# Sheet1.net
KiCad netlist of a schematic drawn in Altium Designer
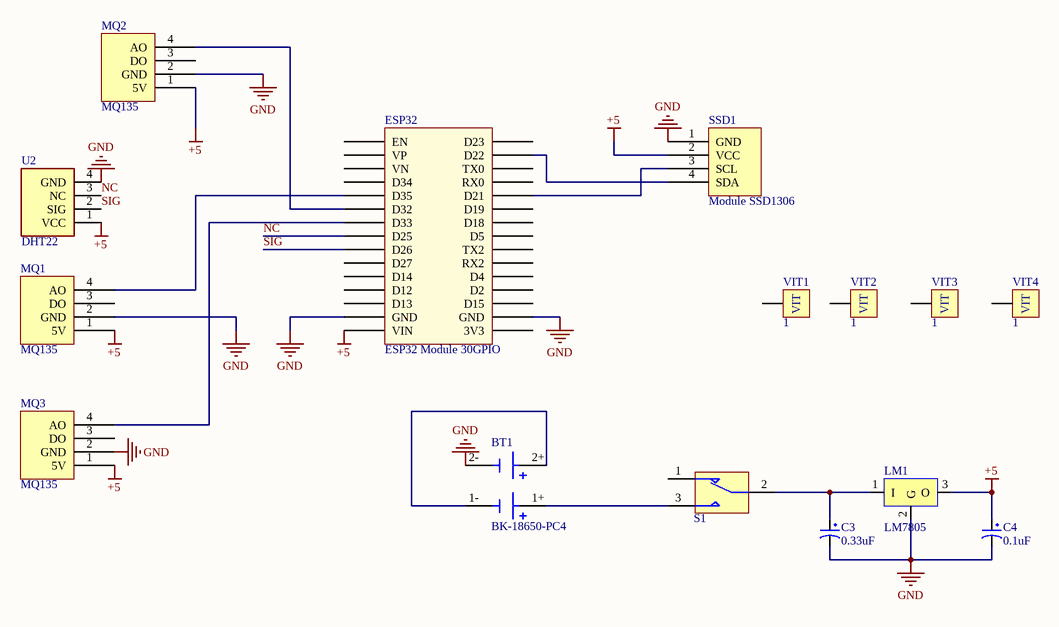
[diagram p0: Sheet1.SchDoc]

(export (version "E")
  (design (tool "Eeschema 10.0.6"))
  (components
    (comp (ref "BT1")
      (value "BK-18650-PC4")
      (footprint "BAT_BK-18650-PC4")
      (description "Battery Holder (Open) 18650 2 Cell PC Pin")
      (libsource (lib "MrKoi_Lib_Sch") (part "BK-18650-PC4"))
    )
    (comp (ref "C3")
      (value "0.33uF")
      (footprint "tu hoa 5mm")
      (description "Cắm")
      (libsource (lib "Tu dien") (part "Tu Hoa 0.33uF 50V 5x11"))
    )
    (comp (ref "C4")
      (value "0.1uF")
      (footprint "tu hoa 5mm")
      (description "Cắm")
      (libsource (lib "Tu dien") (part "Tu Hoa 0.1uF 50V 5x11"))
    )
    (comp (ref "ESP32")
      (value "ESP32 Module 30GPIO")
      (footprint "ESP32 Module 30GPIO_v2")
      (libsource (lib "Module1") (part "ESP32 Module 30GPIO"))
    )
    (comp (ref "LM1")
      (value "LM7805")
      (footprint "TO220NH")
      (description "IC REG LDO 5V 1A TO220-3")
      (libsource (lib "IC") (part "LM78xx"))
    )
    (comp (ref "MQ1")
      (value "MQ135")
      (footprint "MyLibrary:MQ135")
      (libsource (lib "MyLibrary") (part "MQ135"))
    )
    (comp (ref "MQ2")
      (value "MQ135")
      (footprint "MyLibrary:MQ135")
      (libsource (lib "MyLibrary") (part "MQ135"))
    )
    (comp (ref "MQ3")
      (value "MQ135")
      (footprint "MyLibrary:MQ135")
      (libsource (lib "MyLibrary") (part "MQ135"))
    )
    (comp (ref "S1")
      (value "Switch SPDT_Subminiator")
      (footprint "SPDT Subminiator")
      (description "Subminiator SPDT Switch")
      (libsource (lib "iDr.ALTIUM") (part "Switch SPDT_Subminiator"))
    )
    (comp (ref "SSD1")
      (value "Module SSD1306")
      (footprint "Module SSD1306")
      (libsource (lib "MrKoi_Lib_Sch") (part "Module SSD1306"))
    )
    (comp (ref "U2")
      (value "DHT22")
      (footprint "Sensors:DHT22_180")
      (description "SENSOR HUMIDITY/TEMPERATURE")
      (libsource (lib "Sensors") (part "DHT22"))
    )
    (comp (ref "VIT1")
      (value "1")
      (footprint "Screw octagon 3.81mm")
      (description "Vit xuyen lo")
      (libsource (lib "Connector") (part "VIT"))
    )
    (comp (ref "VIT2")
      (value "1")
      (footprint "Screw octagon 3.81mm")
      (description "Vit xuyen lo")
      (libsource (lib "Connector") (part "VIT"))
    )
    (comp (ref "VIT3")
      (value "1")
      (footprint "Screw octagon 3.81mm")
      (description "Vit xuyen lo")
      (libsource (lib "Connector") (part "VIT"))
    )
    (comp (ref "VIT4")
      (value "1")
      (footprint "Screw octagon 3.81mm")
      (description "Vit xuyen lo")
      (libsource (lib "Connector") (part "VIT"))
    )
  )
  (nets
    (net (code "1") (name "+5") (class "Default")
      (node (ref "C4") (pin "1") (pinfunction "1_1") (pintype "passive"))
      (node (ref "ESP32") (pin "30") (pinfunction "VIN_30") (pintype "passive"))
      (node (ref "LM1") (pin "3") (pinfunction "O_3") (pintype "power_in"))
      (node (ref "MQ1") (pin "1") (pinfunction "5V_1") (pintype "passive"))
      (node (ref "MQ2") (pin "1") (pinfunction "5V_1") (pintype "passive"))
      (node (ref "MQ3") (pin "1") (pinfunction "5V_1") (pintype "passive"))
      (node (ref "SSD1") (pin "2") (pinfunction "VCC_2") (pintype "passive"))
      (node (ref "U2") (pin "1") (pinfunction "VCC_1") (pintype "passive"))
    )
    (net (code "2") (name "/NC") (class "Default")
      (node (ref "ESP32") (pin "23") (pinfunction "D25_23") (pintype "passive"))
      (node (ref "U2") (pin "3") (pinfunction "NC_3") (pintype "passive"))
    )
    (net (code "3") (name "/SIG") (class "Default")
      (node (ref "ESP32") (pin "24") (pinfunction "D26_24") (pintype "passive"))
      (node (ref "U2") (pin "2") (pinfunction "SIG_2") (pintype "passive"))
    )
    (net (code "4") (name "GND") (class "Default")
      (node (ref "BT1") (pin "2-") (pinfunction "2-_2-") (pintype "passive"))
      (node (ref "C3") (pin "2") (pinfunction "2_2") (pintype "passive"))
      (node (ref "C4") (pin "2") (pinfunction "2_2") (pintype "passive"))
      (node (ref "ESP32") (pin "14") (pinfunction "GND_14") (pintype "passive"))
      (node (ref "ESP32") (pin "29") (pinfunction "GND_29") (pintype "passive"))
      (node (ref "LM1") (pin "2") (pinfunction "G_2") (pintype "power_in"))
      (node (ref "MQ1") (pin "2") (pinfunction "GND_2") (pintype "passive"))
      (node (ref "MQ2") (pin "2") (pinfunction "GND_2") (pintype "passive"))
      (node (ref "MQ3") (pin "2") (pinfunction "GND_2") (pintype "passive"))
      (node (ref "SSD1") (pin "1") (pinfunction "GND_1") (pintype "passive"))
      (node (ref "U2") (pin "4") (pinfunction "GND_4") (pintype "passive"))
    )
    (net (code "5") (name "Net-(BT1-Pad1+)") (class "Default")
      (node (ref "BT1") (pin "1+") (pinfunction "1+_1+") (pintype "passive"))
      (node (ref "S1") (pin "3") (pinfunction "3_3") (pintype "passive"))
    )
    (net (code "6") (name "Net-(BT1-Pad1-)") (class "Default")
      (node (ref "BT1") (pin "1-") (pinfunction "1-_1-") (pintype "passive"))
      (node (ref "BT1") (pin "2+") (pinfunction "2+_2+") (pintype "passive"))
    )
    (net (code "7") (name "Net-(ESP32-D21)") (class "Default")
      (node (ref "ESP32") (pin "5") (pinfunction "D21_5") (pintype "passive"))
      (node (ref "SSD1") (pin "3") (pinfunction "SCL_3") (pintype "passive"))
    )
    (net (code "8") (name "Net-(ESP32-D22)") (class "Default")
      (node (ref "ESP32") (pin "2") (pinfunction "D22_2") (pintype "passive"))
      (node (ref "SSD1") (pin "4") (pinfunction "SDA_4") (pintype "passive"))
    )
    (net (code "9") (name "Net-(ESP32-D32)") (class "Default")
      (node (ref "ESP32") (pin "21") (pinfunction "D32_21") (pintype "passive"))
      (node (ref "MQ2") (pin "4") (pinfunction "AO_4") (pintype "passive"))
    )
    (net (code "10") (name "Net-(ESP32-D33)") (class "Default")
      (node (ref "ESP32") (pin "22") (pinfunction "D33_22") (pintype "passive"))
      (node (ref "MQ3") (pin "4") (pinfunction "AO_4") (pintype "passive"))
    )
    (net (code "11") (name "Net-(ESP32-D35)") (class "Default")
      (node (ref "ESP32") (pin "20") (pinfunction "D35_20") (pintype "passive"))
      (node (ref "MQ1") (pin "4") (pinfunction "AO_4") (pintype "passive"))
    )
    (net (code "12") (name "Net-(LM1-I)") (class "Default")
      (node (ref "C3") (pin "1") (pinfunction "1_1") (pintype "passive"))
      (node (ref "LM1") (pin "1") (pinfunction "I_1") (pintype "power_in"))
      (node (ref "S1") (pin "2") (pinfunction "2_2") (pintype "passive"))
    )
    (net (code "13") (name "unconnected-(ESP32-3V3-Pad15)") (class "Default")
      (node (ref "ESP32") (pin "15") (pinfunction "3V3_15") (pintype "passive"))
    )
    (net (code "14") (name "unconnected-(ESP32-D2-Pad12)") (class "Default")
      (node (ref "ESP32") (pin "12") (pinfunction "D2_12") (pintype "passive"))
    )
    (net (code "15") (name "unconnected-(ESP32-D4-Pad11)") (class "Default")
      (node (ref "ESP32") (pin "11") (pinfunction "D4_11") (pintype "passive"))
    )
    (net (code "16") (name "unconnected-(ESP32-D5-Pad8)") (class "Default")
      (node (ref "ESP32") (pin "8") (pinfunction "D5_8") (pintype "passive"))
    )
    (net (code "17") (name "unconnected-(ESP32-D12-Pad27)") (class "Default")
      (node (ref "ESP32") (pin "27") (pinfunction "D12_27") (pintype "passive"))
    )
    (net (code "18") (name "unconnected-(ESP32-D13-Pad28)") (class "Default")
      (node (ref "ESP32") (pin "28") (pinfunction "D13_28") (pintype "passive"))
    )
    (net (code "19") (name "unconnected-(ESP32-D14-Pad26)") (class "Default")
      (node (ref "ESP32") (pin "26") (pinfunction "D14_26") (pintype "passive"))
    )
    (net (code "20") (name "unconnected-(ESP32-D15-Pad13)") (class "Default")
      (node (ref "ESP32") (pin "13") (pinfunction "D15_13") (pintype "passive"))
    )
    (net (code "21") (name "unconnected-(ESP32-D18-Pad7)") (class "Default")
      (node (ref "ESP32") (pin "7") (pinfunction "D18_7") (pintype "passive"))
    )
    (net (code "22") (name "unconnected-(ESP32-D19-Pad6)") (class "Default")
      (node (ref "ESP32") (pin "6") (pinfunction "D19_6") (pintype "passive"))
    )
    (net (code "23") (name "unconnected-(ESP32-D23-Pad1)") (class "Default")
      (node (ref "ESP32") (pin "1") (pinfunction "D23_1") (pintype "passive"))
    )
    (net (code "24") (name "unconnected-(ESP32-D27-Pad25)") (class "Default")
      (node (ref "ESP32") (pin "25") (pinfunction "D27_25") (pintype "passive"))
    )
    (net (code "25") (name "unconnected-(ESP32-D34-Pad19)") (class "Default")
      (node (ref "ESP32") (pin "19") (pinfunction "D34_19") (pintype "passive"))
    )
    (net (code "26") (name "unconnected-(ESP32-EN-Pad16)") (class "Default")
      (node (ref "ESP32") (pin "16") (pinfunction "EN_16") (pintype "passive"))
    )
    (net (code "27") (name "unconnected-(ESP32-RX0-Pad4)") (class "Default")
      (node (ref "ESP32") (pin "4") (pinfunction "RX0_4") (pintype "passive"))
    )
    (net (code "28") (name "unconnected-(ESP32-RX2-Pad10)") (class "Default")
      (node (ref "ESP32") (pin "10") (pinfunction "RX2_10") (pintype "passive"))
    )
    (net (code "29") (name "unconnected-(ESP32-TX0-Pad3)") (class "Default")
      (node (ref "ESP32") (pin "3") (pinfunction "TX0_3") (pintype "passive"))
    )
    (net (code "30") (name "unconnected-(ESP32-TX2-Pad9)") (class "Default")
      (node (ref "ESP32") (pin "9") (pinfunction "TX2_9") (pintype "passive"))
    )
    (net (code "31") (name "unconnected-(ESP32-VN-Pad18)") (class "Default")
      (node (ref "ESP32") (pin "18") (pinfunction "VN_18") (pintype "passive"))
    )
    (net (code "32") (name "unconnected-(ESP32-VP-Pad17)") (class "Default")
      (node (ref "ESP32") (pin "17") (pinfunction "VP_17") (pintype "passive"))
    )
    (net (code "33") (name "unconnected-(MQ1-DO-Pad3)") (class "Default")
      (node (ref "MQ1") (pin "3") (pinfunction "DO_3") (pintype "passive"))
    )
    (net (code "34") (name "unconnected-(MQ2-DO-Pad3)") (class "Default")
      (node (ref "MQ2") (pin "3") (pinfunction "DO_3") (pintype "passive"))
    )
    (net (code "35") (name "unconnected-(MQ3-DO-Pad3)") (class "Default")
      (node (ref "MQ3") (pin "3") (pinfunction "DO_3") (pintype "passive"))
    )
    (net (code "36") (name "unconnected-(S1-Pad1)") (class "Default")
      (node (ref "S1") (pin "1") (pinfunction "1_1") (pintype "passive"))
    )
    (net (code "37") (name "unconnected-(VIT1-Pad1)") (class "Default")
      (node (ref "VIT1") (pin "1") (pinfunction "1_1") (pintype "passive"))
    )
    (net (code "38") (name "unconnected-(VIT2-Pad1)") (class "Default")
      (node (ref "VIT2") (pin "1") (pinfunction "1_1") (pintype "passive"))
    )
    (net (code "39") (name "unconnected-(VIT3-Pad1)") (class "Default")
      (node (ref "VIT3") (pin "1") (pinfunction "1_1") (pintype "passive"))
    )
    (net (code "40") (name "unconnected-(VIT4-Pad1)") (class "Default")
      (node (ref "VIT4") (pin "1") (pinfunction "1_1") (pintype "passive"))
    )
  )
)
